# db9-horizontal-autoband.net
KiCad netlist of a schematic drawn in EAGLE
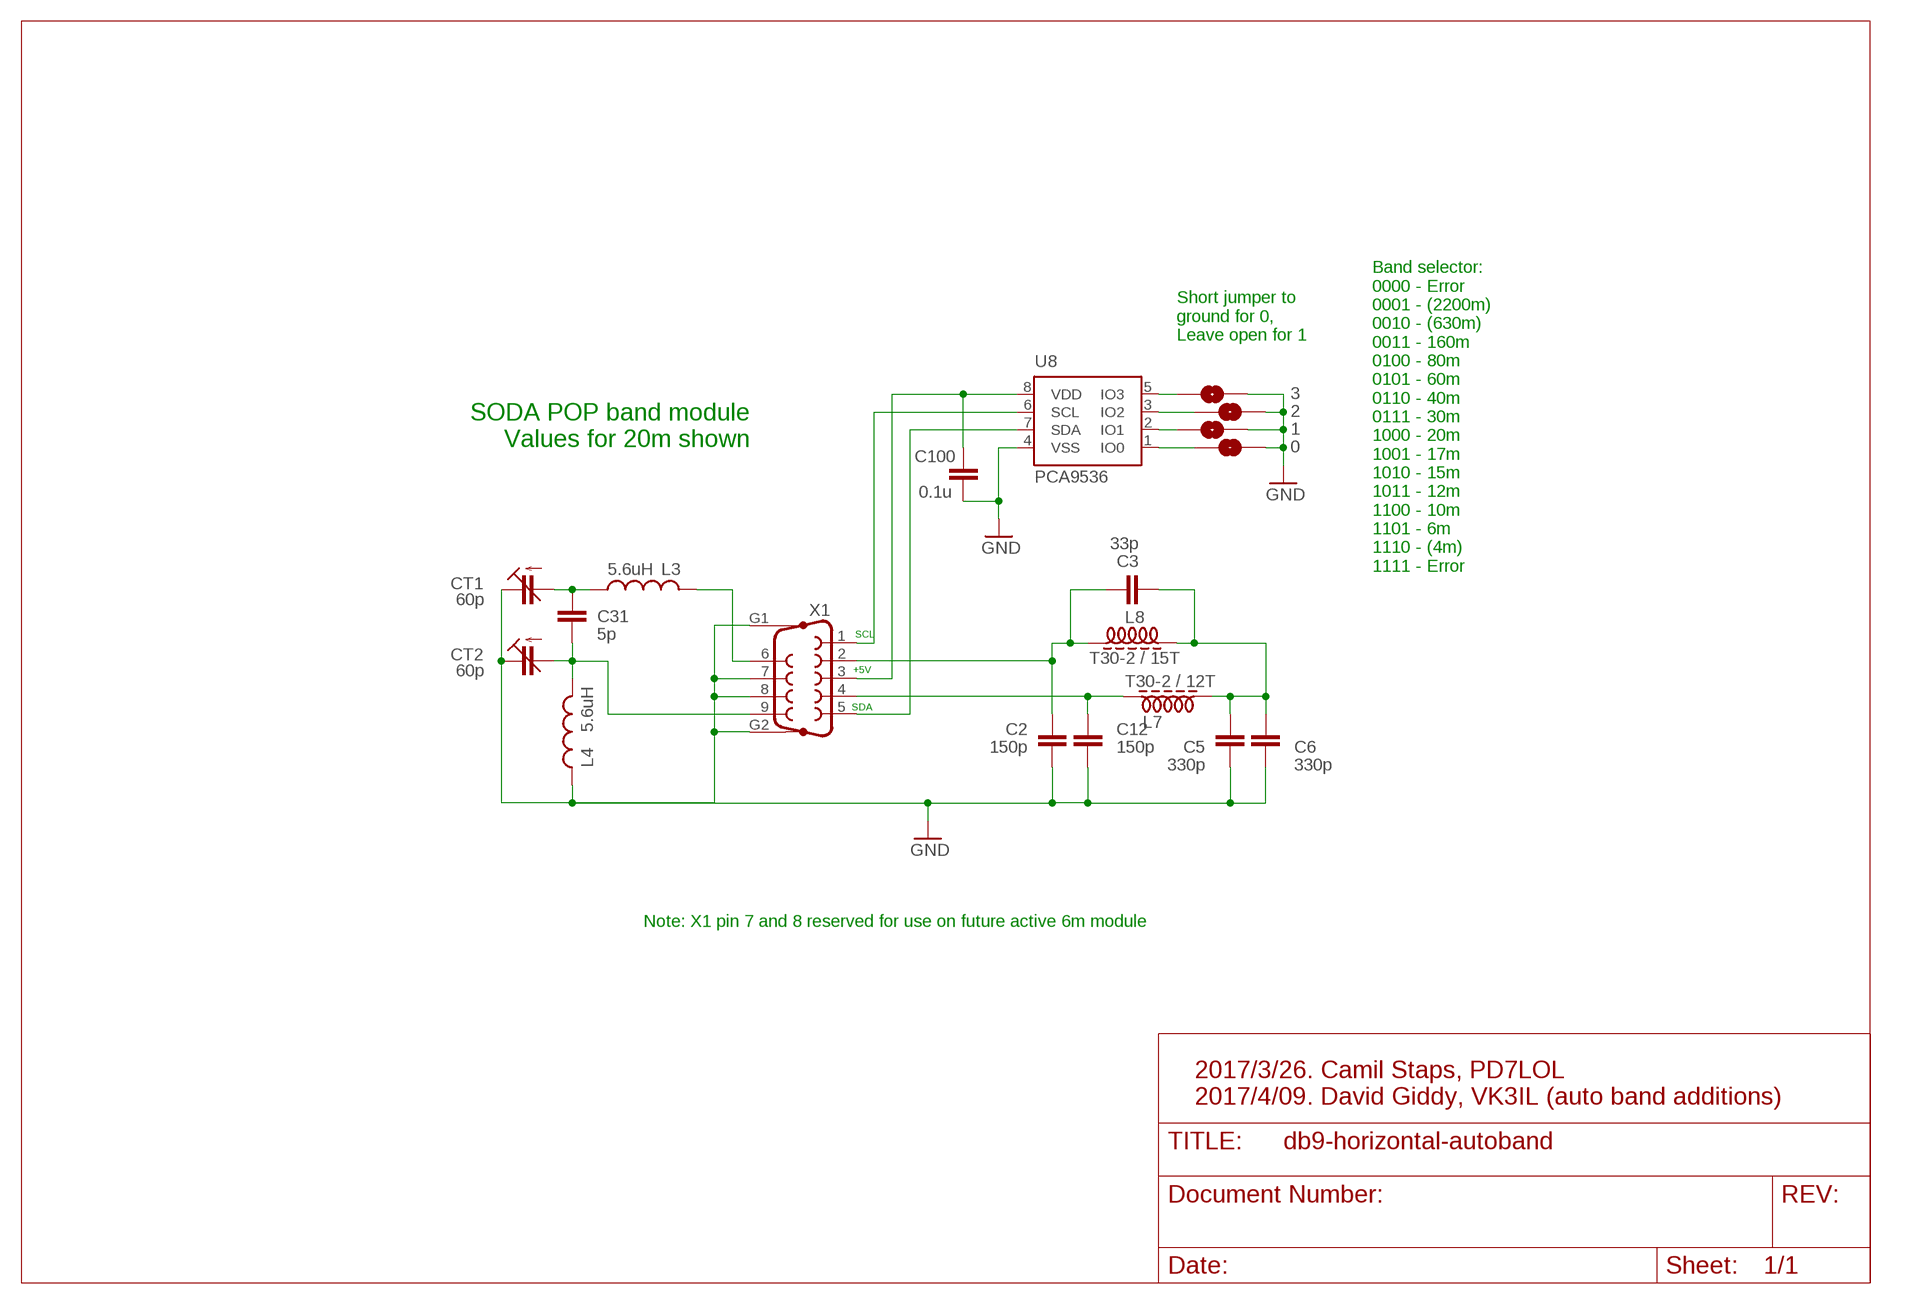
[diagram p0: schematic, sheet 1]

(export (version "E")
  (design (tool "Eeschema 10.0.6"))
  (components
    (comp (ref "0") (value "SJ") (footprint "eagle-import:SJ") (libsource (lib "eagle-import") (part "SJ")))
    (comp (ref "1") (value "SJ") (footprint "eagle-import:SJ") (libsource (lib "eagle-import") (part "SJ")))
    (comp (ref "2") (value "SJ") (footprint "eagle-import:SJ") (libsource (lib "eagle-import") (part "SJ")))
    (comp (ref "3") (value "SJ") (footprint "eagle-import:SJ") (libsource (lib "eagle-import") (part "SJ")))
    (comp (ref "C2")
      (value "150p")
      (footprint "eagle-import:C1206K")
      (libsource (lib "eagle-import") (part "C-EUC1206K"))
    )
    (comp (ref "C3")
      (value "33p")
      (footprint "eagle-import:C1206K")
      (libsource (lib "eagle-import") (part "C-EUC1206K"))
    )
    (comp (ref "C5")
      (value "330p")
      (footprint "eagle-import:C1206K")
      (libsource (lib "eagle-import") (part "C-EUC1206K"))
    )
    (comp (ref "C6")
      (value "330p")
      (footprint "eagle-import:C1206K")
      (libsource (lib "eagle-import") (part "C-EUC1206K"))
    )
    (comp (ref "C12")
      (value "150p")
      (footprint "eagle-import:C1206K")
      (libsource (lib "eagle-import") (part "C-EUC1206K"))
    )
    (comp (ref "C31")
      (value "5p")
      (footprint "eagle-import:C0805K")
      (libsource (lib "eagle-import") (part "C-EUC0805K"))
    )
    (comp (ref "C100")
      (value "0.1u")
      (footprint "eagle-import:C0805K")
      (libsource (lib "eagle-import") (part "C-EUC0805K"))
    )
    (comp (ref "CT1")
      (value "60p")
      (footprint "eagle-import:CTRIMTZ03")
      (libsource (lib "eagle-import") (part "C-TRIMMTZ03"))
    )
    (comp (ref "CT2")
      (value "60p")
      (footprint "eagle-import:CTRIMTZ03")
      (libsource (lib "eagle-import") (part "C-TRIMMTZ03"))
    )
    (comp (ref "L3")
      (value "5.6uH")
      (footprint "eagle-import:L2012C")
      (libsource (lib "eagle-import") (part "L-USL2012C"))
    )
    (comp (ref "L4")
      (value "5.6uH")
      (footprint "eagle-import:L2012C")
      (libsource (lib "eagle-import") (part "L-USL2012C"))
    )
    (comp (ref "L7")
      (value "T30-2 / 12T")
      (footprint "eagle-import:T30-2-28AWG-15T")
      (libsource (lib "eagle-import") (part "INDUCTORT30-2-28AWG-15T"))
    )
    (comp (ref "L8")
      (value "T30-2 / 15T")
      (footprint "eagle-import:T30-2-28AWG-15T")
      (libsource (lib "eagle-import") (part "INDUCTORT30-2-28AWG-15T"))
    )
    (comp (ref "U8")
      (value "PCA9536")
      (footprint "eagle-import:SO8")
      (libsource (lib "eagle-import") (part "PCA9536"))
    )
    (comp (ref "X1")
      (value "F09VP")
      (footprint "eagle-import:F09VP")
      (libsource (lib "eagle-import") (part "F09VP"))
    )
  )
  (nets
    (net (code "1") (name "GND") (class "Default")
      (node (ref "0") (pin "2") (pinfunction "2_2") (pintype "passive"))
      (node (ref "1") (pin "2") (pinfunction "2_2") (pintype "passive"))
      (node (ref "2") (pin "2") (pinfunction "2_2") (pintype "passive"))
      (node (ref "3") (pin "2") (pinfunction "2_2") (pintype "passive"))
      (node (ref "C100") (pin "2") (pinfunction "2_2") (pintype "passive"))
      (node (ref "C12") (pin "2") (pinfunction "2_2") (pintype "passive"))
      (node (ref "C2") (pin "2") (pinfunction "2_2") (pintype "passive"))
      (node (ref "C5") (pin "2") (pinfunction "2_2") (pintype "passive"))
      (node (ref "C6") (pin "2") (pinfunction "2_2") (pintype "passive"))
      (node (ref "CT1") (pin "1") (pinfunction "E_1") (pintype "passive"))
      (node (ref "CT2") (pin "1") (pinfunction "E_1") (pintype "passive"))
      (node (ref "L4") (pin "2") (pinfunction "2_2") (pintype "passive"))
      (node (ref "U8") (pin "4") (pinfunction "VSS_4") (pintype "power_in"))
      (node (ref "X1") (pin "7") (pinfunction "7_7") (pintype "passive"))
      (node (ref "X1") (pin "8") (pinfunction "8_8") (pintype "passive"))
      (node (ref "X1") (pin "G1") (pinfunction "G1_G1") (pintype "passive"))
      (node (ref "X1") (pin "G2") (pinfunction "G2_G2") (pintype "passive"))
    )
    (net (code "2") (name "Net-(CT1-A)") (class "Default")
      (node (ref "C31") (pin "1") (pinfunction "1_1") (pintype "passive"))
      (node (ref "CT1") (pin "2") (pinfunction "A_2") (pintype "passive"))
      (node (ref "L3") (pin "2") (pinfunction "2_2") (pintype "passive"))
    )
    (net (code "3") (name "Net-(CT2-A)") (class "Default")
      (node (ref "C31") (pin "2") (pinfunction "2_2") (pintype "passive"))
      (node (ref "CT2") (pin "2") (pinfunction "A_2") (pintype "passive"))
      (node (ref "L4") (pin "1") (pinfunction "1_1") (pintype "passive"))
      (node (ref "X1") (pin "9") (pinfunction "9_9") (pintype "passive"))
    )
    (net (code "4") (name "Net-(L3-Pad1)") (class "Default")
      (node (ref "L3") (pin "1") (pinfunction "1_1") (pintype "passive"))
      (node (ref "X1") (pin "6") (pinfunction "6_6") (pintype "passive"))
    )
    (net (code "5") (name "Net-(L7-1)") (class "Default")
      (node (ref "C12") (pin "1") (pinfunction "1_1") (pintype "passive"))
      (node (ref "L7") (pin "P$1") (pinfunction "1_P$1") (pintype "passive"))
      (node (ref "X1") (pin "4") (pinfunction "4_4") (pintype "passive"))
    )
    (net (code "6") (name "Net-(L7-2)") (class "Default")
      (node (ref "C3") (pin "2") (pinfunction "2_2") (pintype "passive"))
      (node (ref "C5") (pin "1") (pinfunction "1_1") (pintype "passive"))
      (node (ref "C6") (pin "1") (pinfunction "1_1") (pintype "passive"))
      (node (ref "L7") (pin "P$2") (pinfunction "2_P$2") (pintype "passive"))
      (node (ref "L8") (pin "P$2") (pinfunction "2_P$2") (pintype "passive"))
    )
    (net (code "7") (name "Net-(L8-1)") (class "Default")
      (node (ref "C2") (pin "1") (pinfunction "1_1") (pintype "passive"))
      (node (ref "C3") (pin "1") (pinfunction "1_1") (pintype "passive"))
      (node (ref "L8") (pin "P$1") (pinfunction "1_P$1") (pintype "passive"))
      (node (ref "X1") (pin "2") (pinfunction "2_2") (pintype "passive"))
    )
    (net (code "8") (name "Net-(U8-IO0)") (class "Default")
      (node (ref "0") (pin "1") (pinfunction "1_1") (pintype "passive"))
      (node (ref "U8") (pin "1") (pinfunction "IO0_1") (pintype "bidirectional"))
    )
    (net (code "9") (name "Net-(U8-IO1)") (class "Default")
      (node (ref "1") (pin "1") (pinfunction "1_1") (pintype "passive"))
      (node (ref "U8") (pin "2") (pinfunction "IO1_2") (pintype "bidirectional"))
    )
    (net (code "10") (name "Net-(U8-IO2)") (class "Default")
      (node (ref "2") (pin "1") (pinfunction "1_1") (pintype "passive"))
      (node (ref "U8") (pin "3") (pinfunction "IO2_3") (pintype "bidirectional"))
    )
    (net (code "11") (name "Net-(U8-IO3)") (class "Default")
      (node (ref "3") (pin "1") (pinfunction "1_1") (pintype "passive"))
      (node (ref "U8") (pin "5") (pinfunction "IO3_5") (pintype "bidirectional"))
    )
    (net (code "12") (name "Net-(U8-SCL)") (class "Default")
      (node (ref "U8") (pin "6") (pinfunction "SCL_6") (pintype "input"))
      (node (ref "X1") (pin "1") (pinfunction "1_1") (pintype "passive"))
    )
    (net (code "13") (name "Net-(U8-SDA)") (class "Default")
      (node (ref "U8") (pin "7") (pinfunction "SDA_7") (pintype "bidirectional"))
      (node (ref "X1") (pin "5") (pinfunction "5_5") (pintype "passive"))
    )
    (net (code "14") (name "Net-(U8-VDD)") (class "Default")
      (node (ref "C100") (pin "1") (pinfunction "1_1") (pintype "passive"))
      (node (ref "U8") (pin "8") (pinfunction "VDD_8") (pintype "power_in"))
      (node (ref "X1") (pin "3") (pinfunction "3_3") (pintype "passive"))
    )
  )
)
